# Module_BuckMini_MP2315GJ_5V.net
KiCad netlist of a schematic drawn in Altium Designer
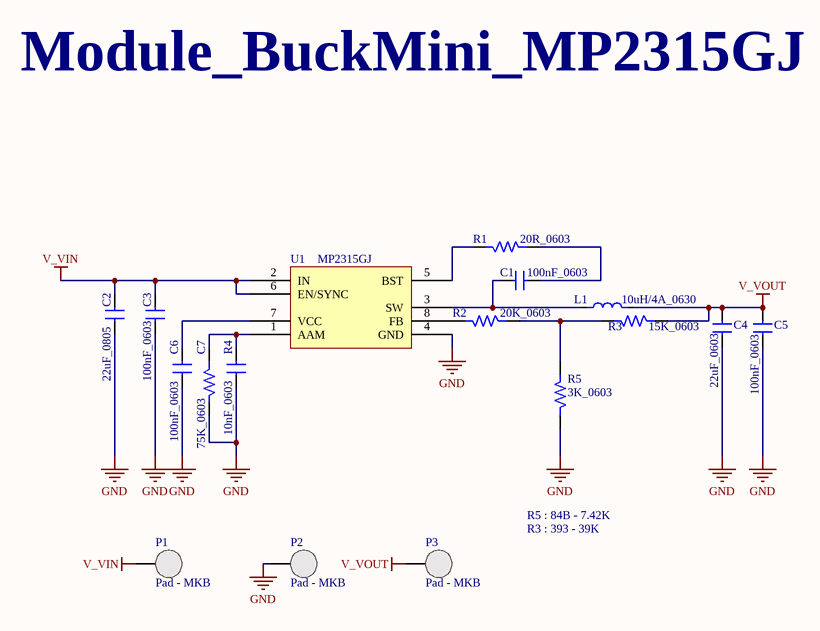
[diagram p0: Module_BuckMini_MP2315GJ_5V.SchDoc]

(export (version "E")
  (design (tool "Eeschema 10.0.6"))
  (components
    (comp (ref "C1")
      (value "100nF_0603")
      (footprint "CN-SMD-0603")
      (description "Cap SMD, 0.06x0.03 inch, 1.55x0.85 mm - 1608")
      (libsource (lib "Passive_MKB") (part "CAP 0603 104"))
    )
    (comp (ref "C2")
      (value "22uF_0805")
      (footprint "CN-SMD-0805 - H50")
      (description "Cap SMD, 0.08x0.05 inch, 2.0x1.2 mm - 2012")
      (libsource (lib "Passive_MKB") (part "CAP 0805 226"))
    )
    (comp (ref "C3")
      (value "100nF_0603")
      (footprint "CN-SMD-0603")
      (description "Cap SMD, 0.06x0.03 inch, 1.55x0.85 mm - 1608")
      (libsource (lib "Passive_MKB") (part "CAP 0603 104"))
    )
    (comp (ref "C4")
      (value "22uF_0603")
      (footprint "CN-SMD-0603")
      (description "Cap SMD, 0.06x0.03 inch, 1.55x0.85 mm - 1608")
      (libsource (lib "Passive_MKB") (part "CAP 0603 226"))
    )
    (comp (ref "C5")
      (value "100nF_0603")
      (footprint "CN-SMD-0603")
      (description "Cap SMD, 0.06x0.03 inch, 1.55x0.85 mm - 1608")
      (libsource (lib "Passive_MKB") (part "CAP 0603 104"))
    )
    (comp (ref "C6")
      (value "100nF_0603")
      (footprint "CN-SMD-0603")
      (description "Cap SMD, 0.06x0.03 inch, 1.55x0.85 mm - 1608")
      (libsource (lib "Passive_MKB") (part "CAP 0603 104"))
    )
    (comp (ref "C7")
      (value "10nF_0603")
      (footprint "CN-SMD-0603")
      (description "Cap SMD, 0.06x0.03 inch, 1.55x0.85 mm - 1608")
      (libsource (lib "Passive_MKB") (part "CAP 0603 103"))
    )
    (comp (ref "L1")
      (value "10uH/4A_0630")
      (footprint "INDUCTOR_0630")
      (description "Inductor")
      (libsource (lib "Passive_MKB") (part "0630 100"))
    )
    (comp (ref "P1")
      (value "Pad - MKB")
      (footprint "Pad  - MKB 2x2.5 (mm)")
      (libsource (lib "JST_MKB") (part "Pad - MKB"))
    )
    (comp (ref "P2")
      (value "Pad - MKB")
      (footprint "Pad  - MKB 2x2.5 (mm)")
      (libsource (lib "JST_MKB") (part "Pad - MKB"))
    )
    (comp (ref "P3")
      (value "Pad - MKB")
      (footprint "Pad  - MKB 2x2.5 (mm)")
      (libsource (lib "JST_MKB") (part "Pad - MKB"))
    )
    (comp (ref "R1")
      (value "20R_0603")
      (footprint "RES-SMD-0603")
      (description "Resistor SMD, 0.06x0.03 inch, 1.55x0.85 mm - 1608, 1/10W")
      (libsource (lib "Passive_MKB") (part "RES 0603 20R"))
    )
    (comp (ref "R2")
      (value "20K_0603")
      (footprint "RES-SMD-0603")
      (description "Resistor SMD, 0.06x0.03 inch, 1.55x0.85 mm - 1608, 1/10W")
      (libsource (lib "Passive_MKB") (part "RES 0603 20K"))
    )
    (comp (ref "R3")
      (value "15K_0603")
      (footprint "RES-SMD-0603")
      (description "Resistor SMD, 0.06x0.03 inch, 1.55x0.85 mm - 1608, 1/10W")
      (libsource (lib "Passive_MKB") (part "RES 0603 15K"))
    )
    (comp (ref "R4")
      (value "75K_0603")
      (footprint "RES-SMD-0603")
      (description "Resistor SMD, 0.06x0.03 inch, 1.55x0.85 mm - 1608, 1/10W")
      (libsource (lib "Passive_MKB") (part "RES 0603 75K"))
    )
    (comp (ref "R5")
      (value "3K_0603")
      (footprint "RES-SMD-0603")
      (description "Resistor SMD, 0.06x0.03 inch, 1.55x0.85 mm - 1608, 1/10W")
      (libsource (lib "Passive_MKB") (part "RES 0603 3K"))
    )
    (comp (ref "U1")
      (value "MP2315GJ")
      (footprint "TSOT-8")
      (description "High Efficiency 3A, 24V, 500kHz\r\n Synchronous Step Down Converter")
      (libsource (lib "IC_MKB") (part "MP2315GJ"))
    )
  )
  (nets
    (net (code "1") (name "GND") (class "Default")
      (node (ref "C2") (pin "1") (pinfunction "1_1") (pintype "passive"))
      (node (ref "C3") (pin "1") (pinfunction "1_1") (pintype "passive"))
      (node (ref "C4") (pin "1") (pinfunction "1_1") (pintype "passive"))
      (node (ref "C5") (pin "1") (pinfunction "1_1") (pintype "passive"))
      (node (ref "C6") (pin "1") (pinfunction "1_1") (pintype "passive"))
      (node (ref "C7") (pin "1") (pinfunction "1_1") (pintype "passive"))
      (node (ref "P2") (pin "0") (pinfunction "PAD_0") (pintype "passive"))
      (node (ref "R4") (pin "1") (pinfunction "1_1") (pintype "passive"))
      (node (ref "R5") (pin "2") (pinfunction "2_2") (pintype "passive"))
      (node (ref "U1") (pin "4") (pinfunction "GND_4") (pintype "passive"))
    )
    (net (code "2") (name "Net-(C1-Pad1)") (class "Default")
      (node (ref "C1") (pin "1") (pinfunction "1_1") (pintype "passive"))
      (node (ref "R1") (pin "2") (pinfunction "2_2") (pintype "passive"))
    )
    (net (code "3") (name "Net-(R2-Pad2)") (class "Default")
      (node (ref "R2") (pin "2") (pinfunction "2_2") (pintype "passive"))
      (node (ref "R3") (pin "1") (pinfunction "1_1") (pintype "passive"))
      (node (ref "R5") (pin "1") (pinfunction "1_1") (pintype "passive"))
    )
    (net (code "4") (name "Net-(U1-AAM)") (class "Default")
      (node (ref "C7") (pin "2") (pinfunction "2_2") (pintype "passive"))
      (node (ref "R4") (pin "2") (pinfunction "2_2") (pintype "passive"))
      (node (ref "U1") (pin "1") (pinfunction "AAM_1") (pintype "passive"))
    )
    (net (code "5") (name "Net-(U1-BST)") (class "Default")
      (node (ref "R1") (pin "1") (pinfunction "1_1") (pintype "passive"))
      (node (ref "U1") (pin "5") (pinfunction "BST_5") (pintype "passive"))
    )
    (net (code "6") (name "Net-(U1-FB)") (class "Default")
      (node (ref "R2") (pin "1") (pinfunction "1_1") (pintype "passive"))
      (node (ref "U1") (pin "8") (pinfunction "FB_8") (pintype "passive"))
    )
    (net (code "7") (name "Net-(U1-SW)") (class "Default")
      (node (ref "C1") (pin "2") (pinfunction "2_2") (pintype "passive"))
      (node (ref "L1") (pin "1") (pinfunction "1_1") (pintype "passive"))
      (node (ref "U1") (pin "3") (pinfunction "SW_3") (pintype "passive"))
    )
    (net (code "8") (name "Net-(U1-VCC)") (class "Default")
      (node (ref "C6") (pin "2") (pinfunction "2_2") (pintype "passive"))
      (node (ref "U1") (pin "7") (pinfunction "VCC_7") (pintype "passive"))
    )
    (net (code "9") (name "V_VIN") (class "Default")
      (node (ref "C2") (pin "2") (pinfunction "2_2") (pintype "passive"))
      (node (ref "C3") (pin "2") (pinfunction "2_2") (pintype "passive"))
      (node (ref "P1") (pin "0") (pinfunction "PAD_0") (pintype "passive"))
      (node (ref "U1") (pin "2") (pinfunction "IN_2") (pintype "passive"))
      (node (ref "U1") (pin "6") (pinfunction "EN/SYNC_6") (pintype "passive"))
    )
    (net (code "10") (name "V_VOUT") (class "Default")
      (node (ref "C4") (pin "2") (pinfunction "2_2") (pintype "passive"))
      (node (ref "C5") (pin "2") (pinfunction "2_2") (pintype "passive"))
      (node (ref "L1") (pin "2") (pinfunction "2_2") (pintype "passive"))
      (node (ref "P3") (pin "0") (pinfunction "PAD_0") (pintype "passive"))
      (node (ref "R3") (pin "2") (pinfunction "2_2") (pintype "passive"))
    )
  )
)
